# power_driver_parallelism.net
KiCad netlist of a schematic drawn in EasyEDA
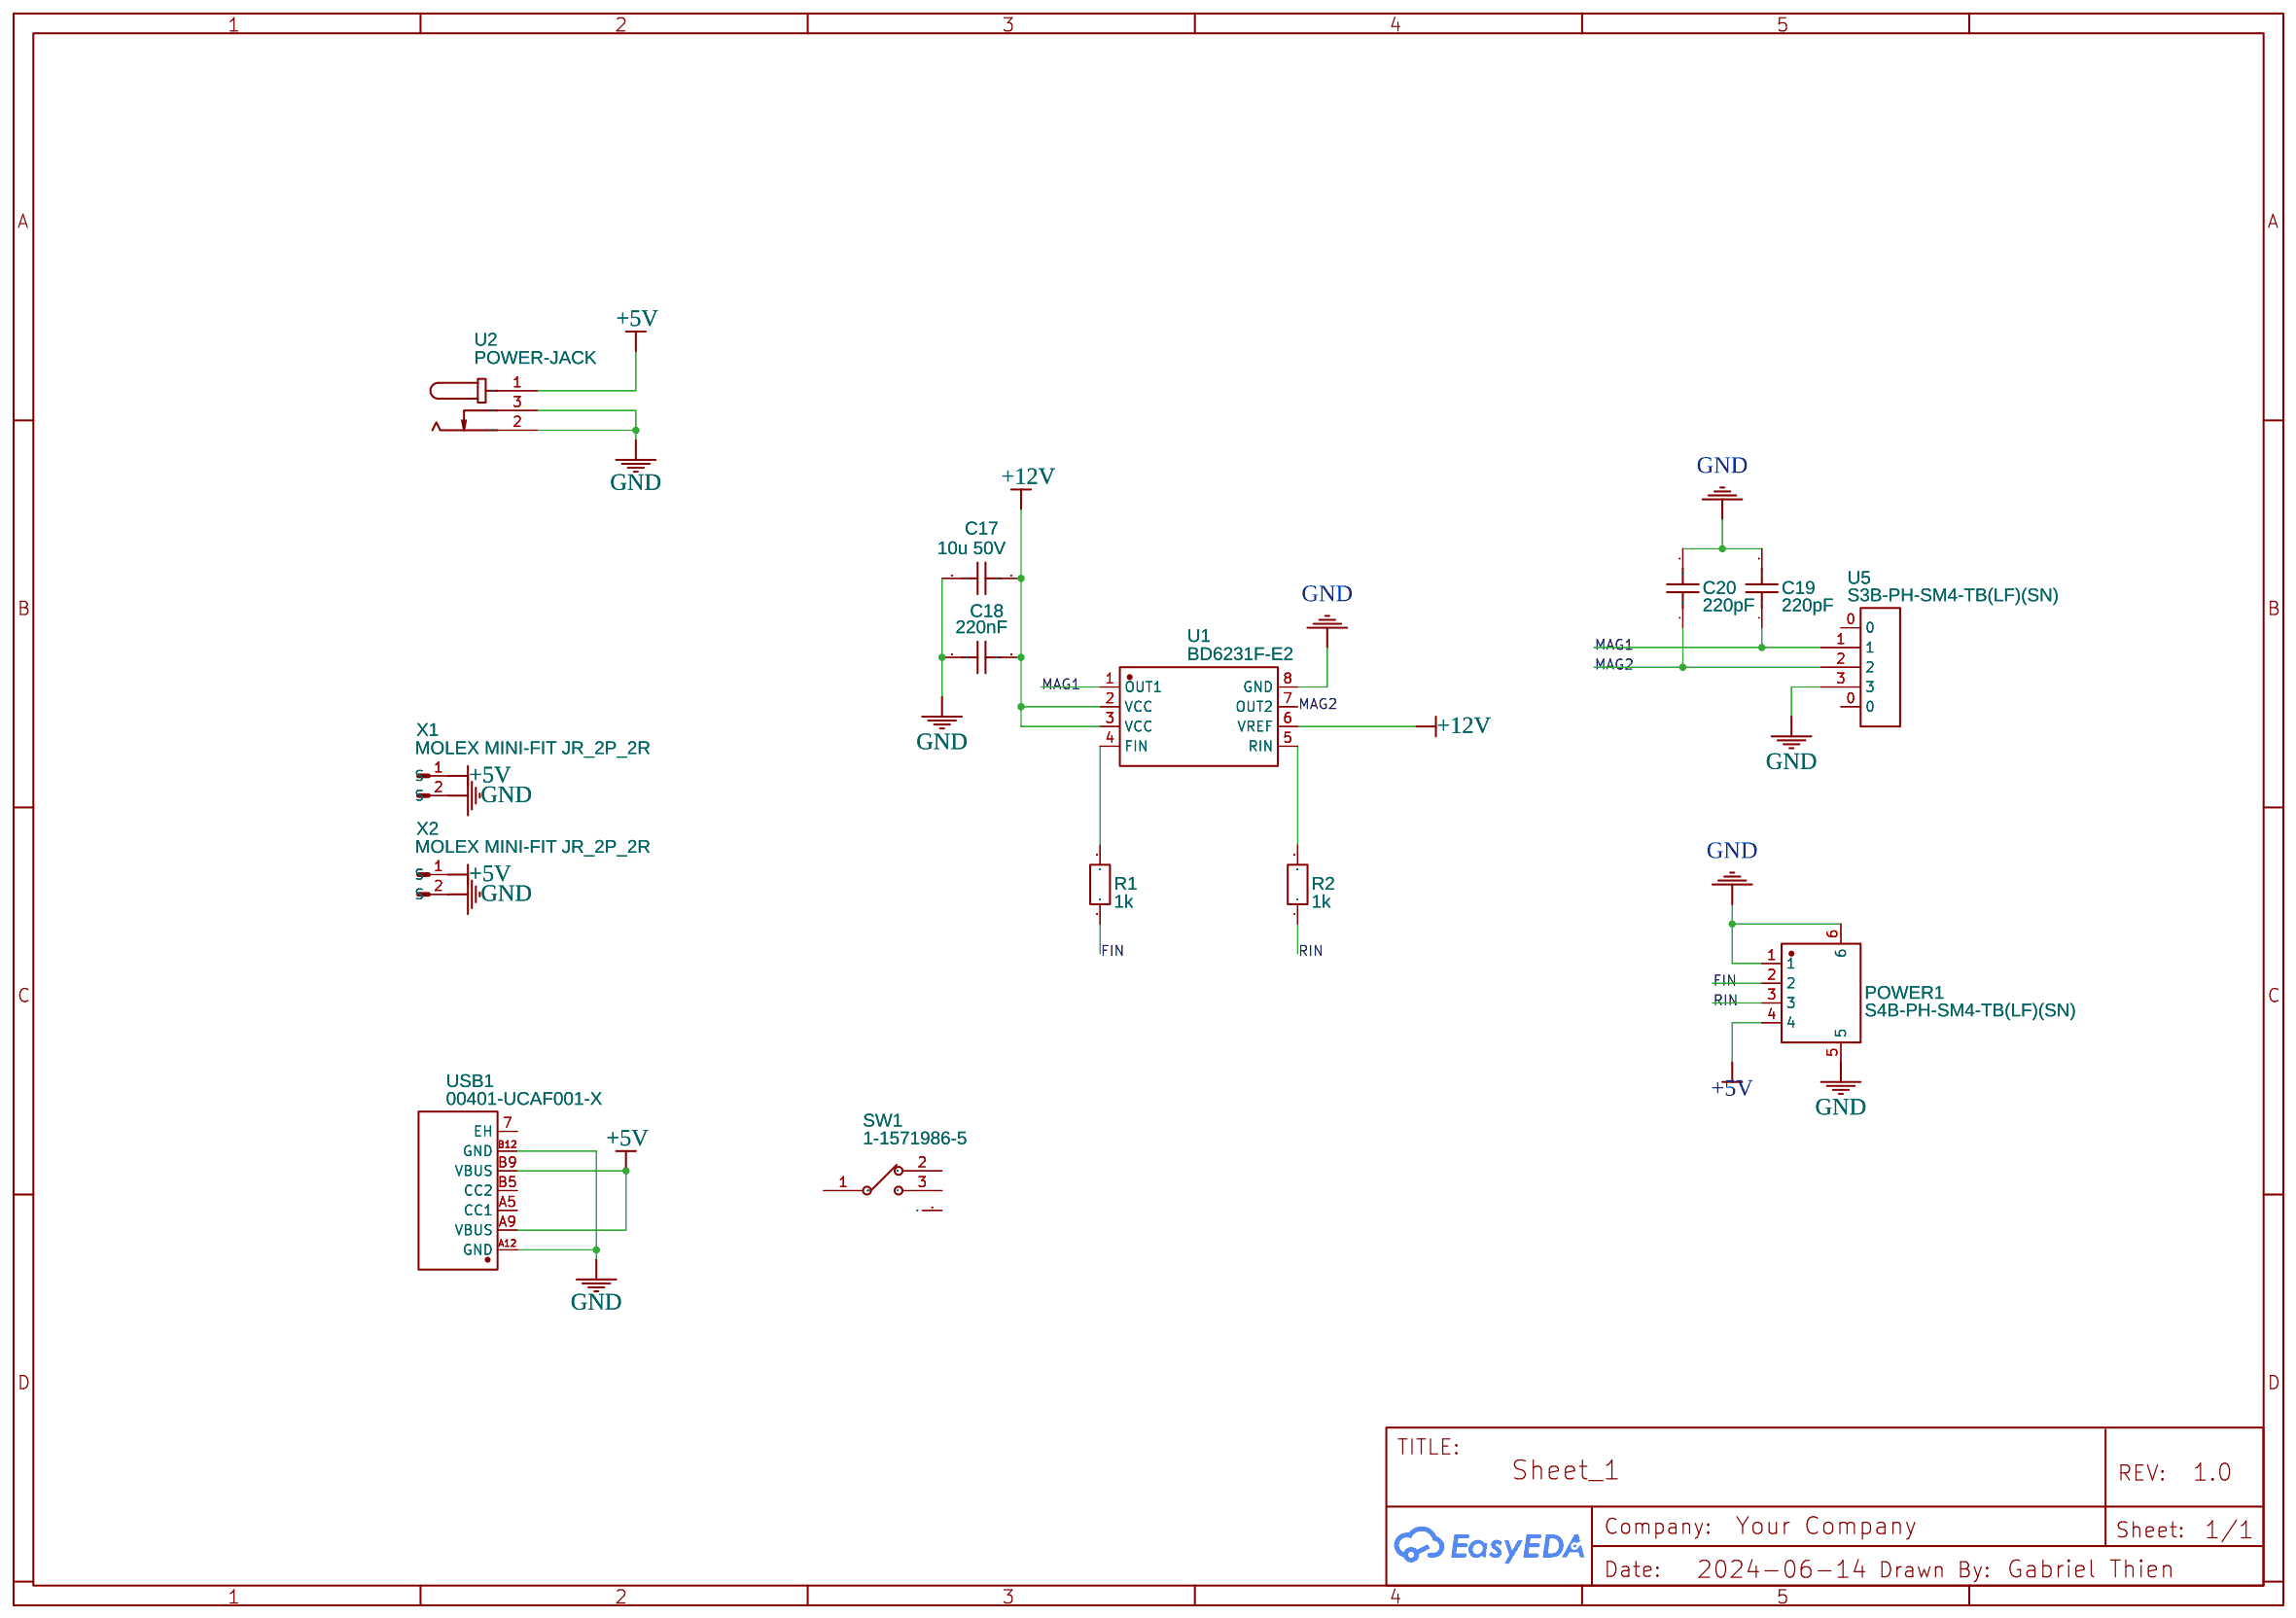
[diagram p0: schematic sheet]

(export (version "E")
  (design (tool "Eeschema 10.0.6"))
  (components
    (comp (ref "C17") (value "10u 50V") (libsource (lib "") (part "C_0603_US_1")))
    (comp (ref "C18") (value "220nF") (libsource (lib "") (part "C_0603_US_1")))
    (comp (ref "C19") (value "220pF") (libsource (lib "") (part "C_0603_US")))
    (comp (ref "C20") (value "220pF") (libsource (lib "") (part "C_0603_US")))
    (comp (ref "POWER1")
      (value "S4B-PH-SM4-TB(LF)(SN)")
      (fields (field (name "Manufacturer") "JST"))
      (libsource (lib "") (part "S4B-PH-SM4-TB(LF)(SN)"))
    )
    (comp (ref "R1") (value "1k") (libsource (lib "") (part "R_0603_EU")))
    (comp (ref "R2") (value "1k") (libsource (lib "") (part "R_0603_EU")))
    (comp (ref "SW1")
      (value "1-1571986-5")
      (fields (field (name "Manufacturer") "TE Connectivity(泰科电子)"))
      (libsource (lib "") (part "1-1571986-5"))
    )
    (comp (ref "U1")
      (value "BD6231F-E2")
      (fields (field (name "Manufacturer") "ROHM(罗姆)"))
      (libsource (lib "") (part "BD6231F-E2"))
    )
    (comp (ref "U2")
      (value "POWER-JACK")
      (fields (field (name "Manufacturer") "索峰"))
      (libsource (lib "") (part "POWER-JACK"))
    )
    (comp (ref "U5")
      (value "S3B-PH-SM4-TB(LF)(SN)")
      (fields (field (name "Manufacturer") "JST"))
      (libsource (lib "") (part "S3B-PH-SM4-TB(LF)(SN)"))
    )
    (comp (ref "USB1")
      (value "00401-UCAF001-X")
      (fields (field (name "Manufacturer") "MINTRON(明硕)"))
      (libsource (lib "") (part "00401-UCAF001-X"))
    )
    (comp (ref "X1")
      (value "MOLEX MINI-FIT JR_2P_2R")
      (fields (field (name "Manufacturer Part") "0026013114") (field (name "Manufacturer") "Molex"))
      (libsource (lib "") (part "MOLEX MINI-FIT JR_2P_2R"))
    )
    (comp (ref "X2")
      (value "MOLEX MINI-FIT JR_2P_2R")
      (fields (field (name "Manufacturer Part") "0026013114") (field (name "Manufacturer") "Molex"))
      (libsource (lib "") (part "MOLEX MINI-FIT JR_2P_2R"))
    )
  )
  (nets
    (net (code "1") (name "+5V") (class "Default")
      (node (ref "POWER1") (pin "4") (pinfunction "4_4") (pintype "unspecified"))
      (node (ref "U2") (pin "1") (pinfunction "1_1") (pintype "unspecified"))
      (node (ref "USB1") (pin "A9") (pinfunction "VBUS_A9") (pintype "unspecified"))
      (node (ref "USB1") (pin "B9") (pinfunction "VBUS_B9") (pintype "unspecified"))
      (node (ref "X1") (pin "1") (pinfunction "S_1") (pintype "bidirectional"))
      (node (ref "X2") (pin "1") (pinfunction "S_1") (pintype "bidirectional"))
    )
    (net (code "2") (name "+12V") (class "Default")
      (node (ref "C17") (pin "2") (pinfunction "2_2") (pintype "unspecified"))
      (node (ref "C18") (pin "2") (pinfunction "2_2") (pintype "unspecified"))
      (node (ref "U1") (pin "2") (pinfunction "VCC_2") (pintype "unspecified"))
      (node (ref "U1") (pin "3") (pinfunction "VCC_3") (pintype "unspecified"))
      (node (ref "U1") (pin "6") (pinfunction "VREF_6") (pintype "unspecified"))
    )
    (net (code "3") (name "/FIN") (class "Default")
      (node (ref "POWER1") (pin "2") (pinfunction "2_2") (pintype "unspecified"))
      (node (ref "R1") (pin "1") (pinfunction "1_1") (pintype "unspecified"))
    )
    (net (code "4") (name "/MAG1") (class "Default")
      (node (ref "C19") (pin "1") (pinfunction "1_1") (pintype "unspecified"))
      (node (ref "U1") (pin "1") (pinfunction "OUT1_1") (pintype "unspecified"))
      (node (ref "U5") (pin "1") (pinfunction "1_1") (pintype "unspecified"))
    )
    (net (code "5") (name "/MAG2") (class "Default")
      (node (ref "C20") (pin "1") (pinfunction "1_1") (pintype "unspecified"))
      (node (ref "U1") (pin "7") (pinfunction "OUT2_7") (pintype "unspecified"))
      (node (ref "U5") (pin "2") (pinfunction "2_2") (pintype "unspecified"))
    )
    (net (code "6") (name "/RIN") (class "Default")
      (node (ref "POWER1") (pin "3") (pinfunction "3_3") (pintype "unspecified"))
      (node (ref "R2") (pin "1") (pinfunction "1_1") (pintype "unspecified"))
    )
    (net (code "7") (name "GND") (class "Default")
      (node (ref "C17") (pin "1") (pinfunction "1_1") (pintype "unspecified"))
      (node (ref "C18") (pin "1") (pinfunction "1_1") (pintype "unspecified"))
      (node (ref "C19") (pin "2") (pinfunction "2_2") (pintype "unspecified"))
      (node (ref "C20") (pin "2") (pinfunction "2_2") (pintype "unspecified"))
      (node (ref "POWER1") (pin "1") (pinfunction "1_1") (pintype "unspecified"))
      (node (ref "POWER1") (pin "5") (pinfunction "5_5") (pintype "unspecified"))
      (node (ref "POWER1") (pin "6") (pinfunction "6_6") (pintype "unspecified"))
      (node (ref "U1") (pin "8") (pinfunction "GND_8") (pintype "unspecified"))
      (node (ref "U2") (pin "2") (pinfunction "2_2") (pintype "unspecified"))
      (node (ref "U2") (pin "3") (pinfunction "3_3") (pintype "unspecified"))
      (node (ref "U5") (pin "3") (pinfunction "3_3") (pintype "unspecified"))
      (node (ref "USB1") (pin "A12") (pinfunction "GND_A12") (pintype "unspecified"))
      (node (ref "USB1") (pin "B12") (pinfunction "GND_B12") (pintype "unspecified"))
      (node (ref "X1") (pin "2") (pinfunction "S_2") (pintype "bidirectional"))
      (node (ref "X2") (pin "2") (pinfunction "S_2") (pintype "bidirectional"))
    )
    (net (code "8") (name "Net-(U1-FIN)") (class "Default")
      (node (ref "R1") (pin "2") (pinfunction "2_2") (pintype "unspecified"))
      (node (ref "U1") (pin "4") (pinfunction "FIN_4") (pintype "unspecified"))
    )
    (net (code "9") (name "Net-(U1-RIN)") (class "Default")
      (node (ref "R2") (pin "2") (pinfunction "2_2") (pintype "unspecified"))
      (node (ref "U1") (pin "5") (pinfunction "RIN_5") (pintype "unspecified"))
    )
    (net (code "10") (name "unconnected-(SW1-COM-Pad1)") (class "Default")
      (node (ref "SW1") (pin "1") (pinfunction "COM_1") (pintype "input"))
    )
    (net (code "11") (name "unconnected-(SW1-Pad0)") (class "Default")
      (node (ref "SW1") (pin "0") (pinfunction "0_0") (pintype "unspecified"))
    )
    (net (code "12") (name "unconnected-(SW1-Pad2)") (class "Default")
      (node (ref "SW1") (pin "2") (pinfunction "2_2") (pintype "input"))
    )
    (net (code "13") (name "unconnected-(SW1-Pad3)") (class "Default")
      (node (ref "SW1") (pin "3") (pinfunction "3_3") (pintype "input"))
    )
    (net (code "14") (name "unconnected-(U5-Pad0)") (class "Default")
      (node (ref "U5") (pin "0") (pinfunction "0_0") (pintype "unspecified"))
    )
    (net (code "15") (name "unconnected-(U5-Pad0)_1") (class "Default")
      (node (ref "U5") (pin "0") (pinfunction "0_0") (pintype "unspecified"))
    )
    (net (code "16") (name "unconnected-(USB1-CC1-PadA5)") (class "Default")
      (node (ref "USB1") (pin "A5") (pinfunction "CC1_A5") (pintype "unspecified"))
    )
    (net (code "17") (name "unconnected-(USB1-CC2-PadB5)") (class "Default")
      (node (ref "USB1") (pin "B5") (pinfunction "CC2_B5") (pintype "unspecified"))
    )
    (net (code "18") (name "unconnected-(USB1-EH-Pad7)") (class "Default")
      (node (ref "USB1") (pin "7") (pinfunction "EH_7") (pintype "unspecified"))
    )
  )
)
